# apollobvm_pcb_mill.net
KiCad netlist of a schematic drawn in EAGLE
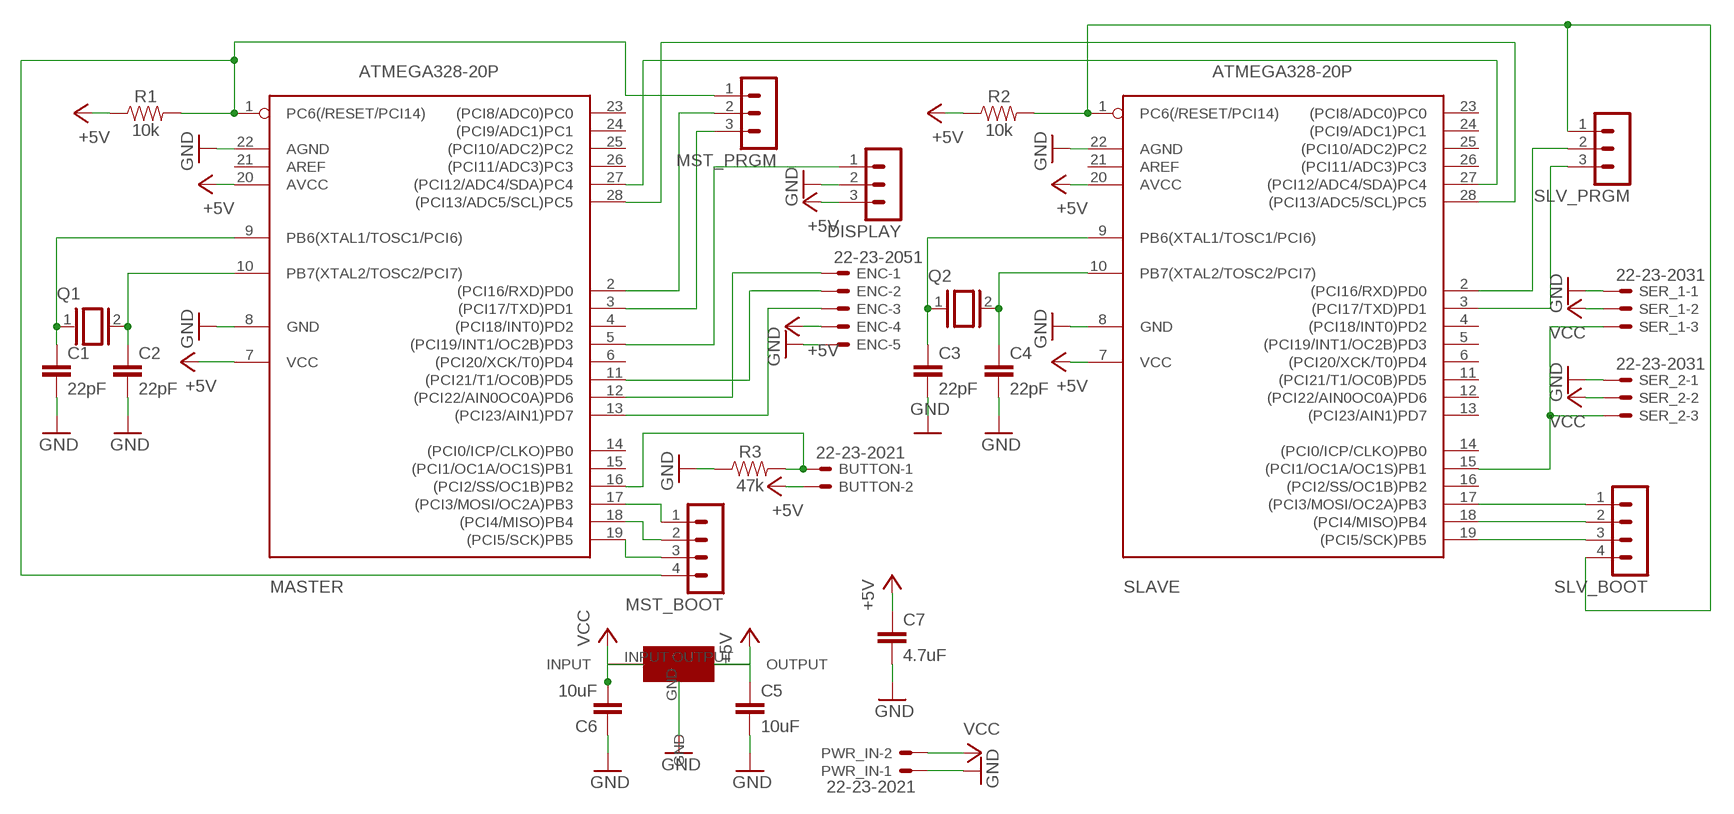
[diagram p0: schematic, sheet 1]

(export (version "E")
  (design (tool "Eeschema 10.0.6"))
  (components
    (comp (ref "BUTTON")
      (value "22-23-2021")
      (footprint "eagle-import:22-23-2021")
      (fields (field (name "MF") "MOLEX"))
      (libsource (lib "eagle-import") (part "22-23-2021"))
    )
    (comp (ref "C1")
      (value "22pF")
      (footprint "eagle-import:0603")
      (libsource (lib "eagle-import") (part "22PF-0603-50V-5%"))
    )
    (comp (ref "C2")
      (value "22pF")
      (footprint "eagle-import:0603")
      (libsource (lib "eagle-import") (part "22PF-0603-50V-5%"))
    )
    (comp (ref "C3")
      (value "22pF")
      (footprint "eagle-import:0603")
      (libsource (lib "eagle-import") (part "22PF-0603-50V-5%"))
    )
    (comp (ref "C4")
      (value "22pF")
      (footprint "eagle-import:0603")
      (libsource (lib "eagle-import") (part "22PF-0603-50V-5%"))
    )
    (comp (ref "C5")
      (value "10uF")
      (footprint "eagle-import:0603")
      (libsource (lib "eagle-import") (part "10UF-0603-6.3V-20%"))
    )
    (comp (ref "C6")
      (value "10uF")
      (footprint "eagle-import:0603")
      (libsource (lib "eagle-import") (part "10UF-0603-6.3V-20%"))
    )
    (comp (ref "C7")
      (value "4.7uF")
      (footprint "eagle-import:0603")
      (libsource (lib "eagle-import") (part "4.7UF0603"))
    )
    (comp (ref "DISPLAY")
      (value "MA03-1")
      (footprint "eagle-import:MA03-1")
      (libsource (lib "eagle-import") (part "MA03-1"))
    )
    (comp (ref "ENC")
      (value "22-23-2051")
      (footprint "eagle-import:22-23-2051")
      (fields (field (name "MF") "MOLEX"))
      (libsource (lib "eagle-import") (part "22-23-2051"))
    )
    (comp (ref "MASTER")
      (value "ATMEGA328-20P")
      (footprint "eagle-import:DIL28-3")
      (libsource (lib "eagle-import") (part "ATMEGA328P-20"))
    )
    (comp (ref "MST_BOOT")
      (value "MA04-1")
      (footprint "eagle-import:MA04-1")
      (libsource (lib "eagle-import") (part "MA04-1"))
    )
    (comp (ref "MST_PRGM")
      (value "MA03-1")
      (footprint "eagle-import:MA03-1")
      (libsource (lib "eagle-import") (part "MA03-1"))
    )
    (comp (ref "PWR_IN")
      (value "22-23-2021")
      (footprint "eagle-import:22-23-2021")
      (fields (field (name "MF") "MOLEX"))
      (libsource (lib "eagle-import") (part "22-23-2021"))
    )
    (comp (ref "Q1")
      (value "XTAL/S")
      (footprint "eagle-import:QS")
      (libsource (lib "eagle-import") (part "XTAL/S"))
    )
    (comp (ref "Q2")
      (value "XTAL/S")
      (footprint "eagle-import:QS")
      (libsource (lib "eagle-import") (part "XTAL/S"))
    )
    (comp (ref "R1")
      (value "10k")
      (footprint "eagle-import:0603")
      (libsource (lib "eagle-import") (part "10KOHM-0603-1/10W-1%"))
    )
    (comp (ref "R2")
      (value "10k")
      (footprint "eagle-import:0603")
      (libsource (lib "eagle-import") (part "10KOHM-0603-1/10W-1%"))
    )
    (comp (ref "R3")
      (value "47k")
      (footprint "eagle-import:0603")
      (libsource (lib "eagle-import") (part "47KOHM-0603-1/10W-1%"))
    )
    (comp (ref "SER_1")
      (value "22-23-2031")
      (footprint "eagle-import:22-23-2031")
      (fields (field (name "MF") "MOLEX"))
      (libsource (lib "eagle-import") (part "22-23-2031"))
    )
    (comp (ref "SER_2")
      (value "22-23-2031")
      (footprint "eagle-import:22-23-2031")
      (fields (field (name "MF") "MOLEX"))
      (libsource (lib "eagle-import") (part "22-23-2031"))
    )
    (comp (ref "SLAVE")
      (value "ATMEGA328-20P")
      (footprint "eagle-import:DIL28-3")
      (libsource (lib "eagle-import") (part "ATMEGA328P-20"))
    )
    (comp (ref "SLV_BOOT")
      (value "MA04-1")
      (footprint "eagle-import:MA04-1")
      (libsource (lib "eagle-import") (part "MA04-1"))
    )
    (comp (ref "SLV_PRGM")
      (value "MA03-1")
      (footprint "eagle-import:MA03-1")
      (libsource (lib "eagle-import") (part "MA03-1"))
    )
    (comp (ref "U$1")
      (value "NCP1117")
      (footprint "eagle-import:NCP1117")
      (libsource (lib "eagle-import") (part "NCP1117"))
    )
  )
  (nets
    (net (code "1") (name "+5V") (class "Default")
      (node (ref "BUTTON") (pin "2") (pinfunction "S_2") (pintype "passive"))
      (node (ref "C5") (pin "1") (pinfunction "1_1") (pintype "passive"))
      (node (ref "C7") (pin "1") (pinfunction "1_1") (pintype "passive"))
      (node (ref "DISPLAY") (pin "3") (pinfunction "3_3") (pintype "passive"))
      (node (ref "ENC") (pin "4") (pinfunction "S_4") (pintype "passive"))
      (node (ref "MASTER") (pin "20") (pinfunction "AVCC_20") (pintype "bidirectional"))
      (node (ref "MASTER") (pin "7") (pinfunction "VCC_7") (pintype "bidirectional"))
      (node (ref "R1") (pin "1") (pinfunction "1_1") (pintype "passive"))
      (node (ref "R2") (pin "1") (pinfunction "1_1") (pintype "passive"))
      (node (ref "SLAVE") (pin "20") (pinfunction "AVCC_20") (pintype "bidirectional"))
      (node (ref "SLAVE") (pin "7") (pinfunction "VCC_7") (pintype "bidirectional"))
      (node (ref "U$1") (pin "OUTPUT") (pinfunction "OUTPUT_OUTPUT") (pintype "bidirectional"))
    )
    (net (code "2") (name "GND") (class "Default")
      (node (ref "C1") (pin "2") (pinfunction "2_2") (pintype "passive"))
      (node (ref "C2") (pin "2") (pinfunction "2_2") (pintype "passive"))
      (node (ref "C3") (pin "2") (pinfunction "2_2") (pintype "passive"))
      (node (ref "C4") (pin "2") (pinfunction "2_2") (pintype "passive"))
      (node (ref "C5") (pin "2") (pinfunction "2_2") (pintype "passive"))
      (node (ref "C6") (pin "1") (pinfunction "1_1") (pintype "passive"))
      (node (ref "C7") (pin "2") (pinfunction "2_2") (pintype "passive"))
      (node (ref "DISPLAY") (pin "2") (pinfunction "2_2") (pintype "passive"))
      (node (ref "ENC") (pin "5") (pinfunction "S_5") (pintype "passive"))
      (node (ref "MASTER") (pin "22") (pinfunction "AGND_22") (pintype "bidirectional"))
      (node (ref "MASTER") (pin "8") (pinfunction "GND_8") (pintype "bidirectional"))
      (node (ref "PWR_IN") (pin "1") (pinfunction "S_1") (pintype "passive"))
      (node (ref "R3") (pin "1") (pinfunction "1_1") (pintype "passive"))
      (node (ref "SER_1") (pin "1") (pinfunction "S_1") (pintype "passive"))
      (node (ref "SER_2") (pin "1") (pinfunction "S_1") (pintype "passive"))
      (node (ref "SLAVE") (pin "22") (pinfunction "AGND_22") (pintype "bidirectional"))
      (node (ref "SLAVE") (pin "8") (pinfunction "GND_8") (pintype "bidirectional"))
      (node (ref "U$1") (pin "GND") (pinfunction "GND_GND") (pintype "bidirectional"))
    )
    (net (code "3") (name "Net-(BUTTONA-S)") (class "Default")
      (node (ref "BUTTON") (pin "1") (pinfunction "S_1") (pintype "passive"))
      (node (ref "MASTER") (pin "16") (pinfunction "(PCI2/SS/OC1B)PB2_16") (pintype "bidirectional"))
      (node (ref "R3") (pin "2") (pinfunction "2_2") (pintype "passive"))
    )
    (net (code "4") (name "Net-(ENCA-S)") (class "Default")
      (node (ref "ENC") (pin "1") (pinfunction "S_1") (pintype "passive"))
      (node (ref "MASTER") (pin "12") (pinfunction "(PCI22/AIN0OC0A)PD6_12") (pintype "bidirectional"))
    )
    (net (code "5") (name "Net-(ENCB-S)") (class "Default")
      (node (ref "ENC") (pin "2") (pinfunction "S_2") (pintype "passive"))
      (node (ref "MASTER") (pin "11") (pinfunction "(PCI21/T1/OC0B)PD5_11") (pintype "bidirectional"))
    )
    (net (code "6") (name "Net-(ENCC-S)") (class "Default")
      (node (ref "ENC") (pin "3") (pinfunction "S_3") (pintype "passive"))
      (node (ref "MASTER") (pin "13") (pinfunction "(PCI23/AIN1)PD7_13") (pintype "bidirectional"))
    )
    (net (code "7") (name "Net-(MASTER-(PCI3{slash}MOSI{slash}OC2A)PB3)") (class "Default")
      (node (ref "MASTER") (pin "17") (pinfunction "(PCI3/MOSI/OC2A)PB3_17") (pintype "bidirectional"))
      (node (ref "MST_BOOT") (pin "1") (pinfunction "1_1") (pintype "passive"))
    )
    (net (code "8") (name "Net-(MASTER-(PCI4{slash}MISO)PB4)") (class "Default")
      (node (ref "MASTER") (pin "18") (pinfunction "(PCI4/MISO)PB4_18") (pintype "bidirectional"))
      (node (ref "MST_BOOT") (pin "2") (pinfunction "2_2") (pintype "passive"))
    )
    (net (code "9") (name "Net-(MASTER-(PCI5{slash}SCK)PB5)") (class "Default")
      (node (ref "MASTER") (pin "19") (pinfunction "(PCI5/SCK)PB5_19") (pintype "bidirectional"))
      (node (ref "MST_BOOT") (pin "3") (pinfunction "3_3") (pintype "passive"))
    )
    (net (code "10") (name "Net-(MASTER-(PCI12{slash}ADC4{slash}SDA)PC4)") (class "Default")
      (node (ref "MASTER") (pin "27") (pinfunction "(PCI12/ADC4/SDA)PC4_27") (pintype "bidirectional"))
      (node (ref "SLAVE") (pin "27") (pinfunction "(PCI12/ADC4/SDA)PC4_27") (pintype "bidirectional"))
    )
    (net (code "11") (name "Net-(MASTER-(PCI13{slash}ADC5{slash}SCL)PC5)") (class "Default")
      (node (ref "MASTER") (pin "28") (pinfunction "(PCI13/ADC5/SCL)PC5_28") (pintype "bidirectional"))
      (node (ref "SLAVE") (pin "28") (pinfunction "(PCI13/ADC5/SCL)PC5_28") (pintype "bidirectional"))
    )
    (net (code "12") (name "Net-(MASTER-(PCI16{slash}RXD)PD0)") (class "Default")
      (node (ref "MASTER") (pin "2") (pinfunction "(PCI16/RXD)PD0_2") (pintype "bidirectional"))
      (node (ref "MST_PRGM") (pin "2") (pinfunction "2_2") (pintype "passive"))
    )
    (net (code "13") (name "Net-(MASTER-(PCI17{slash}TXD)PD1)") (class "Default")
      (node (ref "MASTER") (pin "3") (pinfunction "(PCI17/TXD)PD1_3") (pintype "bidirectional"))
      (node (ref "MST_PRGM") (pin "3") (pinfunction "3_3") (pintype "passive"))
    )
    (net (code "14") (name "Net-(MASTER-(PCI19{slash}INT1{slash}OC2B)PD3)") (class "Default")
      (node (ref "DISPLAY") (pin "1") (pinfunction "1_1") (pintype "passive"))
      (node (ref "MASTER") (pin "5") (pinfunction "(PCI19/INT1/OC2B)PD3_5") (pintype "bidirectional"))
    )
    (net (code "15") (name "Net-(MASTER-PB6(XTAL1{slash}TOSC1{slash}PCI6))") (class "Default")
      (node (ref "C1") (pin "1") (pinfunction "1_1") (pintype "passive"))
      (node (ref "MASTER") (pin "9") (pinfunction "PB6(XTAL1/TOSC1/PCI6)_9") (pintype "bidirectional"))
      (node (ref "Q1") (pin "1") (pinfunction "1_1") (pintype "passive"))
    )
    (net (code "16") (name "Net-(MASTER-PB7(XTAL2{slash}TOSC2{slash}PCI7))") (class "Default")
      (node (ref "C2") (pin "1") (pinfunction "1_1") (pintype "passive"))
      (node (ref "MASTER") (pin "10") (pinfunction "PB7(XTAL2/TOSC2/PCI7)_10") (pintype "bidirectional"))
      (node (ref "Q1") (pin "2") (pinfunction "2_2") (pintype "passive"))
    )
    (net (code "17") (name "Net-(MASTER-PC6({slash}RESET{slash}PCI14))") (class "Default")
      (node (ref "MASTER") (pin "1") (pinfunction "PC6(/RESET/PCI14)_1") (pintype "bidirectional"))
      (node (ref "MST_BOOT") (pin "4") (pinfunction "4_4") (pintype "passive"))
      (node (ref "MST_PRGM") (pin "1") (pinfunction "1_1") (pintype "passive"))
      (node (ref "R1") (pin "2") (pinfunction "2_2") (pintype "passive"))
    )
    (net (code "18") (name "Net-(SER_1C-S)") (class "Default")
      (node (ref "SER_1") (pin "3") (pinfunction "S_3") (pintype "passive"))
      (node (ref "SER_2") (pin "3") (pinfunction "S_3") (pintype "passive"))
      (node (ref "SLAVE") (pin "15") (pinfunction "(PCI1/OC1A/OC1S)PB1_15") (pintype "bidirectional"))
    )
    (net (code "19") (name "Net-(SLAVE-(PCI3{slash}MOSI{slash}OC2A)PB3)") (class "Default")
      (node (ref "SLAVE") (pin "17") (pinfunction "(PCI3/MOSI/OC2A)PB3_17") (pintype "bidirectional"))
      (node (ref "SLV_BOOT") (pin "1") (pinfunction "1_1") (pintype "passive"))
    )
    (net (code "20") (name "Net-(SLAVE-(PCI4{slash}MISO)PB4)") (class "Default")
      (node (ref "SLAVE") (pin "18") (pinfunction "(PCI4/MISO)PB4_18") (pintype "bidirectional"))
      (node (ref "SLV_BOOT") (pin "2") (pinfunction "2_2") (pintype "passive"))
    )
    (net (code "21") (name "Net-(SLAVE-(PCI5{slash}SCK)PB5)") (class "Default")
      (node (ref "SLAVE") (pin "19") (pinfunction "(PCI5/SCK)PB5_19") (pintype "bidirectional"))
      (node (ref "SLV_BOOT") (pin "3") (pinfunction "3_3") (pintype "passive"))
    )
    (net (code "22") (name "Net-(SLAVE-(PCI16{slash}RXD)PD0)") (class "Default")
      (node (ref "SLAVE") (pin "2") (pinfunction "(PCI16/RXD)PD0_2") (pintype "bidirectional"))
      (node (ref "SLV_PRGM") (pin "2") (pinfunction "2_2") (pintype "passive"))
    )
    (net (code "23") (name "Net-(SLAVE-(PCI17{slash}TXD)PD1)") (class "Default")
      (node (ref "SLAVE") (pin "3") (pinfunction "(PCI17/TXD)PD1_3") (pintype "bidirectional"))
      (node (ref "SLV_PRGM") (pin "3") (pinfunction "3_3") (pintype "passive"))
    )
    (net (code "24") (name "Net-(SLAVE-PB6(XTAL1{slash}TOSC1{slash}PCI6))") (class "Default")
      (node (ref "C3") (pin "1") (pinfunction "1_1") (pintype "passive"))
      (node (ref "Q2") (pin "1") (pinfunction "1_1") (pintype "passive"))
      (node (ref "SLAVE") (pin "9") (pinfunction "PB6(XTAL1/TOSC1/PCI6)_9") (pintype "bidirectional"))
    )
    (net (code "25") (name "Net-(SLAVE-PB7(XTAL2{slash}TOSC2{slash}PCI7))") (class "Default")
      (node (ref "C4") (pin "1") (pinfunction "1_1") (pintype "passive"))
      (node (ref "Q2") (pin "2") (pinfunction "2_2") (pintype "passive"))
      (node (ref "SLAVE") (pin "10") (pinfunction "PB7(XTAL2/TOSC2/PCI7)_10") (pintype "bidirectional"))
    )
    (net (code "26") (name "Net-(SLAVE-PC6({slash}RESET{slash}PCI14))") (class "Default")
      (node (ref "R2") (pin "2") (pinfunction "2_2") (pintype "passive"))
      (node (ref "SLAVE") (pin "1") (pinfunction "PC6(/RESET/PCI14)_1") (pintype "bidirectional"))
      (node (ref "SLV_BOOT") (pin "4") (pinfunction "4_4") (pintype "passive"))
      (node (ref "SLV_PRGM") (pin "1") (pinfunction "1_1") (pintype "passive"))
    )
    (net (code "27") (name "VCC") (class "Default")
      (node (ref "C6") (pin "2") (pinfunction "2_2") (pintype "passive"))
      (node (ref "PWR_IN") (pin "2") (pinfunction "S_2") (pintype "passive"))
      (node (ref "SER_1") (pin "2") (pinfunction "S_2") (pintype "passive"))
      (node (ref "SER_2") (pin "2") (pinfunction "S_2") (pintype "passive"))
      (node (ref "U$1") (pin "INPUT") (pinfunction "INPUT_INPUT") (pintype "bidirectional"))
    )
    (net (code "28") (name "unconnected-(MASTER-(PCI0{slash}ICP{slash}CLKO)PB0-Pad14)") (class "Default")
      (node (ref "MASTER") (pin "14") (pinfunction "(PCI0/ICP/CLKO)PB0_14") (pintype "bidirectional"))
    )
    (net (code "29") (name "unconnected-(MASTER-(PCI1{slash}OC1A{slash}OC1S)PB1-Pad15)") (class "Default")
      (node (ref "MASTER") (pin "15") (pinfunction "(PCI1/OC1A/OC1S)PB1_15") (pintype "bidirectional"))
    )
    (net (code "30") (name "unconnected-(MASTER-(PCI8{slash}ADC0)PC0-Pad23)") (class "Default")
      (node (ref "MASTER") (pin "23") (pinfunction "(PCI8/ADC0)PC0_23") (pintype "bidirectional"))
    )
    (net (code "31") (name "unconnected-(MASTER-(PCI9{slash}ADC1)PC1-Pad24)") (class "Default")
      (node (ref "MASTER") (pin "24") (pinfunction "(PCI9/ADC1)PC1_24") (pintype "bidirectional"))
    )
    (net (code "32") (name "unconnected-(MASTER-(PCI10{slash}ADC2)PC2-Pad25)") (class "Default")
      (node (ref "MASTER") (pin "25") (pinfunction "(PCI10/ADC2)PC2_25") (pintype "bidirectional"))
    )
    (net (code "33") (name "unconnected-(MASTER-(PCI11{slash}ADC3)PC3-Pad26)") (class "Default")
      (node (ref "MASTER") (pin "26") (pinfunction "(PCI11/ADC3)PC3_26") (pintype "bidirectional"))
    )
    (net (code "34") (name "unconnected-(MASTER-(PCI18{slash}INT0)PD2-Pad4)") (class "Default")
      (node (ref "MASTER") (pin "4") (pinfunction "(PCI18/INT0)PD2_4") (pintype "bidirectional"))
    )
    (net (code "35") (name "unconnected-(MASTER-(PCI20{slash}XCK{slash}T0)PD4-Pad6)") (class "Default")
      (node (ref "MASTER") (pin "6") (pinfunction "(PCI20/XCK/T0)PD4_6") (pintype "bidirectional"))
    )
    (net (code "36") (name "unconnected-(MASTER-AREF-Pad21)") (class "Default")
      (node (ref "MASTER") (pin "21") (pinfunction "AREF_21") (pintype "bidirectional"))
    )
    (net (code "37") (name "unconnected-(SLAVE-(PCI0{slash}ICP{slash}CLKO)PB0-Pad14)") (class "Default")
      (node (ref "SLAVE") (pin "14") (pinfunction "(PCI0/ICP/CLKO)PB0_14") (pintype "bidirectional"))
    )
    (net (code "38") (name "unconnected-(SLAVE-(PCI2{slash}SS{slash}OC1B)PB2-Pad16)") (class "Default")
      (node (ref "SLAVE") (pin "16") (pinfunction "(PCI2/SS/OC1B)PB2_16") (pintype "bidirectional"))
    )
    (net (code "39") (name "unconnected-(SLAVE-(PCI8{slash}ADC0)PC0-Pad23)") (class "Default")
      (node (ref "SLAVE") (pin "23") (pinfunction "(PCI8/ADC0)PC0_23") (pintype "bidirectional"))
    )
    (net (code "40") (name "unconnected-(SLAVE-(PCI9{slash}ADC1)PC1-Pad24)") (class "Default")
      (node (ref "SLAVE") (pin "24") (pinfunction "(PCI9/ADC1)PC1_24") (pintype "bidirectional"))
    )
    (net (code "41") (name "unconnected-(SLAVE-(PCI10{slash}ADC2)PC2-Pad25)") (class "Default")
      (node (ref "SLAVE") (pin "25") (pinfunction "(PCI10/ADC2)PC2_25") (pintype "bidirectional"))
    )
    (net (code "42") (name "unconnected-(SLAVE-(PCI11{slash}ADC3)PC3-Pad26)") (class "Default")
      (node (ref "SLAVE") (pin "26") (pinfunction "(PCI11/ADC3)PC3_26") (pintype "bidirectional"))
    )
    (net (code "43") (name "unconnected-(SLAVE-(PCI18{slash}INT0)PD2-Pad4)") (class "Default")
      (node (ref "SLAVE") (pin "4") (pinfunction "(PCI18/INT0)PD2_4") (pintype "bidirectional"))
    )
    (net (code "44") (name "unconnected-(SLAVE-(PCI19{slash}INT1{slash}OC2B)PD3-Pad5)") (class "Default")
      (node (ref "SLAVE") (pin "5") (pinfunction "(PCI19/INT1/OC2B)PD3_5") (pintype "bidirectional"))
    )
    (net (code "45") (name "unconnected-(SLAVE-(PCI20{slash}XCK{slash}T0)PD4-Pad6)") (class "Default")
      (node (ref "SLAVE") (pin "6") (pinfunction "(PCI20/XCK/T0)PD4_6") (pintype "bidirectional"))
    )
    (net (code "46") (name "unconnected-(SLAVE-(PCI21{slash}T1{slash}OC0B)PD5-Pad11)") (class "Default")
      (node (ref "SLAVE") (pin "11") (pinfunction "(PCI21/T1/OC0B)PD5_11") (pintype "bidirectional"))
    )
    (net (code "47") (name "unconnected-(SLAVE-(PCI22{slash}AIN0OC0A)PD6-Pad12)") (class "Default")
      (node (ref "SLAVE") (pin "12") (pinfunction "(PCI22/AIN0OC0A)PD6_12") (pintype "bidirectional"))
    )
    (net (code "48") (name "unconnected-(SLAVE-(PCI23{slash}AIN1)PD7-Pad13)") (class "Default")
      (node (ref "SLAVE") (pin "13") (pinfunction "(PCI23/AIN1)PD7_13") (pintype "bidirectional"))
    )
    (net (code "49") (name "unconnected-(SLAVE-AREF-Pad21)") (class "Default")
      (node (ref "SLAVE") (pin "21") (pinfunction "AREF_21") (pintype "bidirectional"))
    )
  )
)
